# pa.net
KiCad netlist of a schematic drawn in Altium Designer
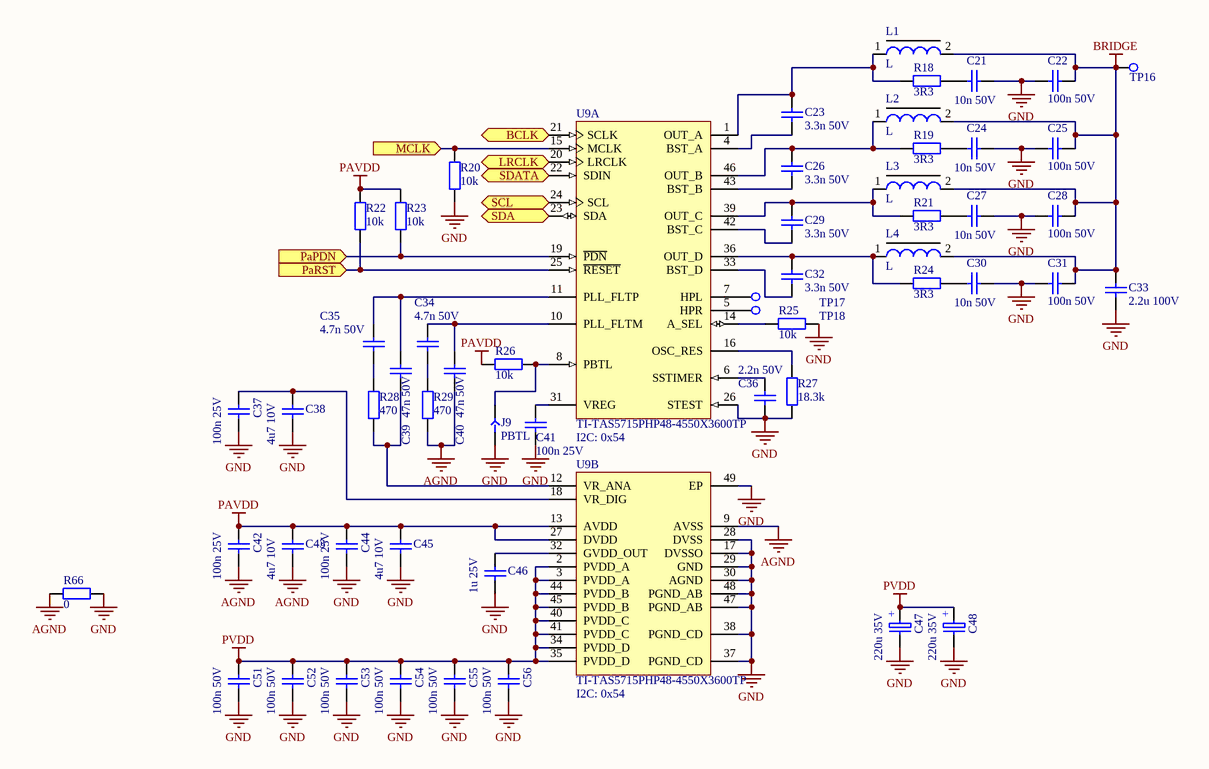
[diagram p0: pa.SchDoc]

(export (version "E")
  (design (tool "Eeschema 10.0.6"))
  (components
    (comp (ref "C21")
      (value "10n 50V")
      (footprint "C-0603-H")
      (description "Capacitor 10nF 50V")
      (libsource (lib "Passives") (part "C-0603-10n-50V"))
    )
    (comp (ref "C22")
      (value "100n 50V")
      (footprint "C-0805-H")
      (libsource (lib "Passives") (part "C-0805-100n-50V"))
    )
    (comp (ref "C23")
      (value "3.3n 50V")
      (footprint "C-0603-H")
      (description "Capacitor 3.3n 50V")
      (libsource (lib "Passives") (part "C-0603-3n3-50V"))
    )
    (comp (ref "C24")
      (value "10n 50V")
      (footprint "C-0603-H")
      (description "Capacitor 10nF 50V")
      (libsource (lib "Passives") (part "C-0603-10n-50V"))
    )
    (comp (ref "C25")
      (value "100n 50V")
      (footprint "C-0805-H")
      (libsource (lib "Passives") (part "C-0805-100n-50V"))
    )
    (comp (ref "C26")
      (value "3.3n 50V")
      (footprint "C-0603-H")
      (description "Capacitor 3.3n 50V")
      (libsource (lib "Passives") (part "C-0603-3n3-50V"))
    )
    (comp (ref "C27")
      (value "10n 50V")
      (footprint "C-0603-H")
      (description "Capacitor 10nF 50V")
      (libsource (lib "Passives") (part "C-0603-10n-50V"))
    )
    (comp (ref "C28")
      (value "100n 50V")
      (footprint "C-0805-H")
      (libsource (lib "Passives") (part "C-0805-100n-50V"))
    )
    (comp (ref "C29")
      (value "3.3n 50V")
      (footprint "C-0603-H")
      (description "Capacitor 3.3n 50V")
      (libsource (lib "Passives") (part "C-0603-3n3-50V"))
    )
    (comp (ref "C30")
      (value "10n 50V")
      (footprint "C-0603-H")
      (description "Capacitor 10nF 50V")
      (libsource (lib "Passives") (part "C-0603-10n-50V"))
    )
    (comp (ref "C31")
      (value "100n 50V")
      (footprint "C-0805-H")
      (libsource (lib "Passives") (part "C-0805-100n-50V"))
    )
    (comp (ref "C32")
      (value "3.3n 50V")
      (footprint "C-0603-H")
      (description "Capacitor 3.3n 50V")
      (libsource (lib "Passives") (part "C-0603-3n3-50V"))
    )
    (comp (ref "C33")
      (value "2.2u 100V")
      (footprint "C-1210-M")
      (description "Capacitor 2.2uF 100V")
      (libsource (lib "Passives") (part "C-1210-2u2-100V"))
    )
    (comp (ref "C34")
      (value "4.7n 50V")
      (footprint "C-0603-H")
      (description "Capacitor 4.7n 50V")
      (libsource (lib "Passives") (part "C-0603-4n7-50V"))
    )
    (comp (ref "C35")
      (value "4.7n 50V")
      (footprint "C-0603-H")
      (description "Capacitor 4.7n 50V")
      (libsource (lib "Passives") (part "C-0603-4n7-50V"))
    )
    (comp (ref "C36")
      (value "2.2n 50V")
      (footprint "C-0603-H")
      (description "Capacitor 2.2n 50V")
      (libsource (lib "Passives") (part "C-0603-2n2-50V"))
    )
    (comp (ref "C37")
      (value "100n 25V")
      (footprint "C-0603-H")
      (description "Capacitor 100n 25V")
      (libsource (lib "Passives") (part "C-0603-100n-25V"))
    )
    (comp (ref "C38")
      (value "4u7 10V")
      (footprint "C-0603-H")
      (description "Capacitor 4.7uF 10V")
      (libsource (lib "Passives") (part "C-0603-4u7-10V"))
    )
    (comp (ref "C39")
      (value "47n 50V")
      (footprint "C-0603-M")
      (description "Capacitor 47nF 50V")
      (libsource (lib "Passives") (part "C-0603-47n-50V_1"))
    )
    (comp (ref "C40")
      (value "47n 50V")
      (footprint "C-0603-M")
      (description "Capacitor 47nF 50V")
      (libsource (lib "Passives") (part "C-0603-47n-50V_1"))
    )
    (comp (ref "C41")
      (value "100n 25V")
      (footprint "C-0603-H")
      (description "Capacitor 100n 25V")
      (libsource (lib "Passives") (part "C-0603-100n-25V"))
    )
    (comp (ref "C42")
      (value "100n 25V")
      (footprint "C-0603-H")
      (description "Capacitor 100n 25V")
      (libsource (lib "Passives") (part "C-0603-100n-25V"))
    )
    (comp (ref "C43")
      (value "4u7 10V")
      (footprint "C-0603-H")
      (description "Capacitor 4.7uF 10V")
      (libsource (lib "Passives") (part "C-0603-4u7-10V"))
    )
    (comp (ref "C44")
      (value "100n 25V")
      (footprint "C-0603-H")
      (description "Capacitor 100n 25V")
      (libsource (lib "Passives") (part "C-0603-100n-25V"))
    )
    (comp (ref "C45")
      (value "4u7 10V")
      (footprint "C-0603-H")
      (description "Capacitor 4.7uF 10V")
      (libsource (lib "Passives") (part "C-0603-4u7-10V"))
    )
    (comp (ref "C46")
      (value "1u 25V")
      (footprint "C-0603-H")
      (description "Capacitor 1uF 25V")
      (libsource (lib "Passives") (part "C-0603-1u-25V"))
    )
    (comp (ref "C47")
      (value "220u 35V")
      (footprint "SMD-10x10")
      (description "electrolytic capacitor 220u 35V")
      (libsource (lib "Passives") (part "CE-SMD-220u-35V"))
    )
    (comp (ref "C48")
      (value "220u 35V")
      (footprint "SMD-10x10")
      (description "electrolytic capacitor 220u 35V")
      (libsource (lib "Passives") (part "CE-SMD-220u-35V"))
    )
    (comp (ref "C51")
      (value "100n 50V")
      (footprint "C-0603-H")
      (description "Capacitor 100n 50V")
      (libsource (lib "Passives") (part "C-0603-100n-50V"))
    )
    (comp (ref "C52")
      (value "100n 50V")
      (footprint "C-0603-H")
      (description "Capacitor 100n 50V")
      (libsource (lib "Passives") (part "C-0603-100n-50V"))
    )
    (comp (ref "C53")
      (value "100n 50V")
      (footprint "C-0603-H")
      (description "Capacitor 100n 50V")
      (libsource (lib "Passives") (part "C-0603-100n-50V"))
    )
    (comp (ref "C54")
      (value "100n 50V")
      (footprint "C-0603-H")
      (description "Capacitor 100n 50V")
      (libsource (lib "Passives") (part "C-0603-100n-50V"))
    )
    (comp (ref "C55")
      (value "100n 50V")
      (footprint "C-0603-H")
      (description "Capacitor 100n 50V")
      (libsource (lib "Passives") (part "C-0603-100n-50V"))
    )
    (comp (ref "C56")
      (value "100n 50V")
      (footprint "C-0603-H")
      (description "Capacitor 100n 50V")
      (libsource (lib "Passives") (part "C-0603-100n-50V"))
    )
    (comp (ref "J9") (value "PBTL") (footprint "jmpr") (libsource (lib "400PT160_2") (part "jmpr")))
    (comp (ref "L1") (value "L") (footprint "L-SDR1105") (libsource (lib "advanced") (part "L")))
    (comp (ref "L2") (value "L") (footprint "L-SDR1105") (libsource (lib "advanced") (part "L")))
    (comp (ref "L3") (value "L") (footprint "L-SDR1105") (libsource (lib "advanced") (part "L")))
    (comp (ref "L4") (value "L") (footprint "L-SDR1105") (libsource (lib "advanced") (part "L")))
    (comp (ref "R18")
      (value "3R3")
      (footprint "R-0603-H")
      (description "Resistor 3R3")
      (libsource (lib "Passives") (part "R-0603-3R3"))
    )
    (comp (ref "R19")
      (value "3R3")
      (footprint "R-0603-H")
      (description "Resistor 3R3")
      (libsource (lib "Passives") (part "R-0603-3R3"))
    )
    (comp (ref "R20")
      (value "10k")
      (footprint "R-0603-H")
      (description "Resistor 10k")
      (libsource (lib "Passives") (part "R-0603-10k"))
    )
    (comp (ref "R21")
      (value "3R3")
      (footprint "R-0603-H")
      (description "Resistor 3R3")
      (libsource (lib "Passives") (part "R-0603-3R3"))
    )
    (comp (ref "R22")
      (value "10k")
      (footprint "R-0603-H")
      (description "Resistor 10k")
      (libsource (lib "Passives") (part "R-0603-10k"))
    )
    (comp (ref "R23")
      (value "10k")
      (footprint "R-0603-H")
      (description "Resistor 10k")
      (libsource (lib "Passives") (part "R-0603-10k"))
    )
    (comp (ref "R24")
      (value "3R3")
      (footprint "R-0603-H")
      (description "Resistor 3R3")
      (libsource (lib "Passives") (part "R-0603-3R3"))
    )
    (comp (ref "R25")
      (value "10k")
      (footprint "R-0603-H")
      (description "Resistor 10k")
      (libsource (lib "") (part "R-0603-10k_1"))
    )
    (comp (ref "R26")
      (value "10k")
      (footprint "R-0603-H")
      (description "Resistor 10k")
      (libsource (lib "") (part "R-0603-10k_1"))
    )
    (comp (ref "R27")
      (value "18.3k")
      (footprint "R-0603-M")
      (description "Resistor 18.3k")
      (libsource (lib "Passives") (part "R-0603-18k3"))
    )
    (comp (ref "R28")
      (value "470")
      (footprint "R-0603-H")
      (description "Resistor 470")
      (libsource (lib "Passives") (part "R-0603-470"))
    )
    (comp (ref "R29")
      (value "470")
      (footprint "R-0603-H")
      (description "Resistor 470")
      (libsource (lib "Passives") (part "R-0603-470"))
    )
    (comp (ref "R66")
      (value "0")
      (footprint "R-0603-M")
      (description "Resistor 0")
      (libsource (lib "Passives") (part "R-0603-0"))
    )
    (comp (ref "TP16") (value "TP-SMD") (footprint "TP") (libsource (lib "advanced") (part "TP-SMD")))
    (comp (ref "TP17") (value "TP-SMD") (footprint "TP") (libsource (lib "advanced") (part "TP-SMD")))
    (comp (ref "TP18") (value "TP-SMD") (footprint "TP") (libsource (lib "advanced") (part "TP-SMD")))
    (comp (ref "U9")
      (value "TI-TAS5715PHP48-4550X3600TP")
      (footprint "TI-PHP48-4550X3600TP_N")
      (libsource (lib "advanced") (part "TI-TAS5715PHP48-4550X3600TP"))
    )
  )
  (nets
    (net (code "1") (name "/BCLK") (class "Default")
      (node (ref "U9") (pin "21") (pinfunction "SCLK_21") (pintype "input"))
    )
    (net (code "2") (name "/LRCLK") (class "Default")
      (node (ref "U9") (pin "20") (pinfunction "LRCLK_20") (pintype "input"))
    )
    (net (code "3") (name "/MCLK") (class "Default")
      (node (ref "R20") (pin "2") (pinfunction "2_2") (pintype "passive"))
      (node (ref "U9") (pin "15") (pinfunction "MCLK_15") (pintype "input"))
    )
    (net (code "4") (name "/PaPDN") (class "Default")
      (node (ref "R23") (pin "1") (pinfunction "1_1") (pintype "passive"))
      (node (ref "U9") (pin "19") (pinfunction "~{PDN}_19") (pintype "input"))
    )
    (net (code "5") (name "/PaRST") (class "Default")
      (node (ref "R22") (pin "1") (pinfunction "1_1") (pintype "passive"))
      (node (ref "U9") (pin "25") (pinfunction "~{RESET}_25") (pintype "input"))
    )
    (net (code "6") (name "/SCL") (class "Default")
      (node (ref "U9") (pin "24") (pinfunction "SCL_24") (pintype "input"))
    )
    (net (code "7") (name "/SDA") (class "Default")
      (node (ref "U9") (pin "23") (pinfunction "SDA_23") (pintype "bidirectional"))
    )
    (net (code "8") (name "/SDATA") (class "Default")
      (node (ref "U9") (pin "22") (pinfunction "SDIN_22") (pintype "input"))
    )
    (net (code "9") (name "AGND") (class "Default")
      (node (ref "C40") (pin "1") (pinfunction "1_1") (pintype "passive"))
      (node (ref "C42") (pin "1") (pinfunction "1_1") (pintype "passive"))
      (node (ref "C43") (pin "1") (pinfunction "1_1") (pintype "passive"))
      (node (ref "R29") (pin "1") (pinfunction "1_1") (pintype "passive"))
      (node (ref "R66") (pin "1") (pinfunction "1_1") (pintype "passive"))
      (node (ref "U9") (pin "9") (pinfunction "AVSS_9") (pintype "power_in"))
    )
    (net (code "10") (name "BRIDGE") (class "Default")
      (node (ref "C22") (pin "1") (pinfunction "1_1") (pintype "passive"))
      (node (ref "C25") (pin "1") (pinfunction "1_1") (pintype "passive"))
      (node (ref "C28") (pin "1") (pinfunction "1_1") (pintype "passive"))
      (node (ref "C31") (pin "1") (pinfunction "1_1") (pintype "passive"))
      (node (ref "C33") (pin "1") (pinfunction "1_1") (pintype "passive"))
      (node (ref "L1") (pin "2") (pinfunction "2_2") (pintype "passive"))
      (node (ref "L2") (pin "2") (pinfunction "2_2") (pintype "passive"))
      (node (ref "L3") (pin "2") (pinfunction "2_2") (pintype "passive"))
      (node (ref "L4") (pin "2") (pinfunction "2_2") (pintype "passive"))
      (node (ref "TP16") (pin "1") (pintype "passive"))
    )
    (net (code "11") (name "GND") (class "Default")
      (node (ref "C21") (pin "1") (pinfunction "1_1") (pintype "passive"))
      (node (ref "C22") (pin "2") (pinfunction "2_2") (pintype "passive"))
      (node (ref "C24") (pin "1") (pinfunction "1_1") (pintype "passive"))
      (node (ref "C25") (pin "2") (pinfunction "2_2") (pintype "passive"))
      (node (ref "C27") (pin "1") (pinfunction "1_1") (pintype "passive"))
      (node (ref "C28") (pin "2") (pinfunction "2_2") (pintype "passive"))
      (node (ref "C30") (pin "1") (pinfunction "1_1") (pintype "passive"))
      (node (ref "C31") (pin "2") (pinfunction "2_2") (pintype "passive"))
      (node (ref "C33") (pin "2") (pinfunction "2_2") (pintype "passive"))
      (node (ref "C36") (pin "2") (pinfunction "2_2") (pintype "passive"))
      (node (ref "C37") (pin "1") (pinfunction "1_1") (pintype "passive"))
      (node (ref "C38") (pin "1") (pinfunction "1_1") (pintype "passive"))
      (node (ref "C41") (pin "1") (pinfunction "1_1") (pintype "passive"))
      (node (ref "C44") (pin "1") (pinfunction "1_1") (pintype "passive"))
      (node (ref "C45") (pin "1") (pinfunction "1_1") (pintype "passive"))
      (node (ref "C46") (pin "1") (pinfunction "1_1") (pintype "passive"))
      (node (ref "C47") (pin "1") (pinfunction "1_1") (pintype "passive"))
      (node (ref "C48") (pin "1") (pinfunction "1_1") (pintype "passive"))
      (node (ref "C51") (pin "1") (pinfunction "1_1") (pintype "passive"))
      (node (ref "C52") (pin "1") (pinfunction "1_1") (pintype "passive"))
      (node (ref "C53") (pin "1") (pinfunction "1_1") (pintype "passive"))
      (node (ref "C54") (pin "1") (pinfunction "1_1") (pintype "passive"))
      (node (ref "C55") (pin "1") (pinfunction "1_1") (pintype "passive"))
      (node (ref "C56") (pin "1") (pinfunction "1_1") (pintype "passive"))
      (node (ref "J9") (pin "1") (pinfunction "1_1") (pintype "passive"))
      (node (ref "R20") (pin "1") (pinfunction "1_1") (pintype "passive"))
      (node (ref "R25") (pin "2") (pinfunction "2_2") (pintype "passive"))
      (node (ref "R27") (pin "1") (pinfunction "1_1") (pintype "passive"))
      (node (ref "R66") (pin "2") (pinfunction "2_2") (pintype "passive"))
      (node (ref "U9") (pin "17") (pinfunction "DVSSO_17") (pintype "power_in"))
      (node (ref "U9") (pin "26") (pinfunction "STEST_26") (pintype "input"))
      (node (ref "U9") (pin "28") (pinfunction "DVSS_28") (pintype "power_in"))
      (node (ref "U9") (pin "29") (pinfunction "GND_29") (pintype "power_in"))
      (node (ref "U9") (pin "30") (pinfunction "AGND_30") (pintype "power_in"))
      (node (ref "U9") (pin "37") (pinfunction "PGND_CD_37") (pintype "power_in"))
      (node (ref "U9") (pin "38") (pinfunction "PGND_CD_38") (pintype "power_in"))
      (node (ref "U9") (pin "47") (pinfunction "PGND_AB_47") (pintype "power_in"))
      (node (ref "U9") (pin "48") (pinfunction "PGND_AB_48") (pintype "power_in"))
      (node (ref "U9") (pin "49") (pinfunction "EP_49") (pintype "passive"))
    )
    (net (code "12") (name "Net-(C21-Pad2)") (class "Default")
      (node (ref "C21") (pin "2") (pinfunction "2_2") (pintype "passive"))
      (node (ref "R18") (pin "1") (pinfunction "1_1") (pintype "passive"))
    )
    (net (code "13") (name "Net-(C24-Pad2)") (class "Default")
      (node (ref "C24") (pin "2") (pinfunction "2_2") (pintype "passive"))
      (node (ref "R19") (pin "1") (pinfunction "1_1") (pintype "passive"))
    )
    (net (code "14") (name "Net-(C27-Pad2)") (class "Default")
      (node (ref "C27") (pin "2") (pinfunction "2_2") (pintype "passive"))
      (node (ref "R21") (pin "1") (pinfunction "1_1") (pintype "passive"))
    )
    (net (code "15") (name "Net-(C30-Pad2)") (class "Default")
      (node (ref "C30") (pin "2") (pinfunction "2_2") (pintype "passive"))
      (node (ref "R24") (pin "1") (pinfunction "1_1") (pintype "passive"))
    )
    (net (code "16") (name "Net-(C34-Pad1)") (class "Default")
      (node (ref "C34") (pin "1") (pinfunction "1_1") (pintype "passive"))
      (node (ref "R29") (pin "2") (pinfunction "2_2") (pintype "passive"))
    )
    (net (code "17") (name "Net-(C35-Pad1)") (class "Default")
      (node (ref "C35") (pin "1") (pinfunction "1_1") (pintype "passive"))
      (node (ref "R28") (pin "2") (pinfunction "2_2") (pintype "passive"))
    )
    (net (code "18") (name "Net-(U9A-A_SEL)") (class "Default")
      (node (ref "R25") (pin "1") (pinfunction "1_1") (pintype "passive"))
      (node (ref "U9") (pin "14") (pinfunction "A_SEL_14") (pintype "bidirectional"))
    )
    (net (code "19") (name "Net-(U9A-BST_A)") (class "Default")
      (node (ref "C23") (pin "1") (pinfunction "1_1") (pintype "passive"))
      (node (ref "U9") (pin "4") (pinfunction "BST_A_4") (pintype "passive"))
    )
    (net (code "20") (name "Net-(U9A-BST_B)") (class "Default")
      (node (ref "C26") (pin "1") (pinfunction "1_1") (pintype "passive"))
      (node (ref "U9") (pin "43") (pinfunction "BST_B_43") (pintype "passive"))
    )
    (net (code "21") (name "Net-(U9A-BST_C)") (class "Default")
      (node (ref "C29") (pin "1") (pinfunction "1_1") (pintype "passive"))
      (node (ref "U9") (pin "42") (pinfunction "BST_C_42") (pintype "passive"))
    )
    (net (code "22") (name "Net-(U9A-BST_D)") (class "Default")
      (node (ref "C32") (pin "1") (pinfunction "1_1") (pintype "passive"))
      (node (ref "U9") (pin "33") (pinfunction "BST_D_33") (pintype "passive"))
    )
    (net (code "23") (name "Net-(U9A-HPL)") (class "Default")
      (node (ref "TP17") (pin "1") (pintype "passive"))
      (node (ref "U9") (pin "7") (pinfunction "HPL_7") (pintype "tri_state"))
    )
    (net (code "24") (name "Net-(U9A-HPR)") (class "Default")
      (node (ref "TP18") (pin "1") (pintype "passive"))
      (node (ref "U9") (pin "5") (pinfunction "HPR_5") (pintype "tri_state"))
    )
    (net (code "25") (name "Net-(U9A-OSC_RES)") (class "Default")
      (node (ref "R27") (pin "2") (pinfunction "2_2") (pintype "passive"))
      (node (ref "U9") (pin "16") (pinfunction "OSC_RES_16") (pintype "passive"))
    )
    (net (code "26") (name "Net-(U9A-OUT_A)") (class "Default")
      (node (ref "C23") (pin "2") (pinfunction "2_2") (pintype "passive"))
      (node (ref "L1") (pin "1") (pinfunction "1_1") (pintype "passive"))
      (node (ref "R18") (pin "2") (pinfunction "2_2") (pintype "passive"))
      (node (ref "U9") (pin "1") (pinfunction "OUT_A_1") (pintype "tri_state"))
    )
    (net (code "27") (name "Net-(U9A-OUT_B)") (class "Default")
      (node (ref "C26") (pin "2") (pinfunction "2_2") (pintype "passive"))
      (node (ref "L2") (pin "1") (pinfunction "1_1") (pintype "passive"))
      (node (ref "R19") (pin "2") (pinfunction "2_2") (pintype "passive"))
      (node (ref "U9") (pin "46") (pinfunction "OUT_B_46") (pintype "tri_state"))
    )
    (net (code "28") (name "Net-(U9A-OUT_C)") (class "Default")
      (node (ref "C29") (pin "2") (pinfunction "2_2") (pintype "passive"))
      (node (ref "L3") (pin "1") (pinfunction "1_1") (pintype "passive"))
      (node (ref "R21") (pin "2") (pinfunction "2_2") (pintype "passive"))
      (node (ref "U9") (pin "39") (pinfunction "OUT_C_39") (pintype "tri_state"))
    )
    (net (code "29") (name "Net-(U9A-OUT_D)") (class "Default")
      (node (ref "C32") (pin "2") (pinfunction "2_2") (pintype "passive"))
      (node (ref "L4") (pin "1") (pinfunction "1_1") (pintype "passive"))
      (node (ref "R24") (pin "2") (pinfunction "2_2") (pintype "passive"))
      (node (ref "U9") (pin "36") (pinfunction "OUT_D_36") (pintype "tri_state"))
    )
    (net (code "30") (name "Net-(U9A-PBTL)") (class "Default")
      (node (ref "J9") (pin "2") (pinfunction "2_2") (pintype "passive"))
      (node (ref "R26") (pin "2") (pinfunction "2_2") (pintype "passive"))
      (node (ref "U9") (pin "8") (pinfunction "PBTL_8") (pintype "input"))
    )
    (net (code "31") (name "Net-(U9A-PLL_FLTM)") (class "Default")
      (node (ref "C34") (pin "2") (pinfunction "2_2") (pintype "passive"))
      (node (ref "C40") (pin "2") (pinfunction "2_2") (pintype "passive"))
      (node (ref "U9") (pin "10") (pinfunction "PLL_FLTM_10") (pintype "passive"))
    )
    (net (code "32") (name "Net-(U9A-PLL_FLTP)") (class "Default")
      (node (ref "C35") (pin "2") (pinfunction "2_2") (pintype "passive"))
      (node (ref "C39") (pin "2") (pinfunction "2_2") (pintype "passive"))
      (node (ref "U9") (pin "11") (pinfunction "PLL_FLTP_11") (pintype "passive"))
    )
    (net (code "33") (name "Net-(U9A-SSTIMER)") (class "Default")
      (node (ref "C36") (pin "1") (pinfunction "1_1") (pintype "passive"))
      (node (ref "U9") (pin "6") (pinfunction "SSTIMER_6") (pintype "input"))
    )
    (net (code "34") (name "Net-(U9A-VREG)") (class "Default")
      (node (ref "C41") (pin "2") (pinfunction "2_2") (pintype "passive"))
      (node (ref "U9") (pin "31") (pinfunction "VREG_31") (pintype "passive"))
    )
    (net (code "35") (name "Net-(U9B-GVDD_OUT)") (class "Default")
      (node (ref "C46") (pin "2") (pinfunction "2_2") (pintype "passive"))
      (node (ref "U9") (pin "32") (pinfunction "GVDD_OUT_32") (pintype "power_in"))
    )
    (net (code "36") (name "Net-(U9B-VR_ANA)") (class "Default")
      (node (ref "C39") (pin "1") (pinfunction "1_1") (pintype "passive"))
      (node (ref "R28") (pin "1") (pinfunction "1_1") (pintype "passive"))
      (node (ref "U9") (pin "12") (pinfunction "VR_ANA_12") (pintype "power_in"))
    )
    (net (code "37") (name "Net-(U9B-VR_DIG)") (class "Default")
      (node (ref "C37") (pin "2") (pinfunction "2_2") (pintype "passive"))
      (node (ref "C38") (pin "2") (pinfunction "2_2") (pintype "passive"))
      (node (ref "U9") (pin "18") (pinfunction "VR_DIG_18") (pintype "power_in"))
    )
    (net (code "38") (name "PAVDD") (class "Default")
      (node (ref "C42") (pin "2") (pinfunction "2_2") (pintype "passive"))
      (node (ref "C43") (pin "2") (pinfunction "2_2") (pintype "passive"))
      (node (ref "C44") (pin "2") (pinfunction "2_2") (pintype "passive"))
      (node (ref "C45") (pin "2") (pinfunction "2_2") (pintype "passive"))
      (node (ref "R22") (pin "2") (pinfunction "2_2") (pintype "passive"))
      (node (ref "R23") (pin "2") (pinfunction "2_2") (pintype "passive"))
      (node (ref "R26") (pin "1") (pinfunction "1_1") (pintype "passive"))
      (node (ref "U9") (pin "13") (pinfunction "AVDD_13") (pintype "power_in"))
      (node (ref "U9") (pin "27") (pinfunction "DVDD_27") (pintype "power_in"))
    )
    (net (code "39") (name "PVDD") (class "Default")
      (node (ref "C47") (pin "2") (pinfunction "2_2") (pintype "passive"))
      (node (ref "C48") (pin "2") (pinfunction "2_2") (pintype "passive"))
      (node (ref "C51") (pin "2") (pinfunction "2_2") (pintype "passive"))
      (node (ref "C52") (pin "2") (pinfunction "2_2") (pintype "passive"))
      (node (ref "C53") (pin "2") (pinfunction "2_2") (pintype "passive"))
      (node (ref "C54") (pin "2") (pinfunction "2_2") (pintype "passive"))
      (node (ref "C55") (pin "2") (pinfunction "2_2") (pintype "passive"))
      (node (ref "C56") (pin "2") (pinfunction "2_2") (pintype "passive"))
      (node (ref "U9") (pin "2") (pinfunction "PVDD_A_2") (pintype "power_in"))
      (node (ref "U9") (pin "3") (pinfunction "PVDD_A_3") (pintype "power_in"))
      (node (ref "U9") (pin "34") (pinfunction "PVDD_D_34") (pintype "power_in"))
      (node (ref "U9") (pin "35") (pinfunction "PVDD_D_35") (pintype "power_in"))
      (node (ref "U9") (pin "40") (pinfunction "PVDD_C_40") (pintype "power_in"))
      (node (ref "U9") (pin "41") (pinfunction "PVDD_C_41") (pintype "power_in"))
      (node (ref "U9") (pin "44") (pinfunction "PVDD_B_44") (pintype "power_in"))
      (node (ref "U9") (pin "45") (pinfunction "PVDD_B_45") (pintype "power_in"))
    )
  )
)
